# Gyro.net
KiCad netlist of a schematic drawn in Altium Designer
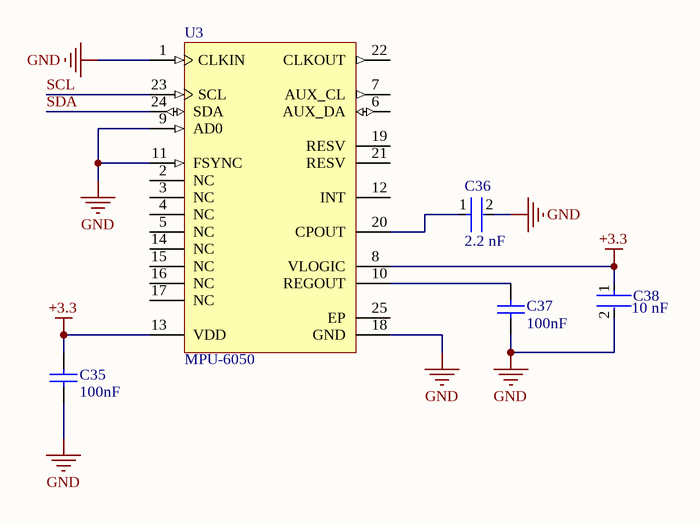
[diagram p0: Gyro.SchDoc]

(export (version "E")
  (design (tool "Eeschema 10.0.6"))
  (components
    (comp (ref "C35")
      (value "CL05B104KO5NNNC")
      (footprint "CAPC1050X55X23ML05T13")
      (description "Chip Capacitor, 100 nF, +/- 10%, 16 V, -55 to 125 degC, 0402 (1005 Metric), RoHS, Tape and Reel")
      (fields (field (name "MANUFACTURER") "Samsung Electro-Mechanics") (field (name "CAPACITANCE") "100nF"))
      (libsource (lib "Altium Content Vault") (part "CAP-NP-2"))
    )
    (comp (ref "C36")
      (value "CC0402KRX7R9BB222")
      (footprint "FP-CC0402-MFG")
      (description "CAP CER 2200PF 50V X7R 0402")
      (fields
        (field (name "TOLERANCE") "0.1")
        (field (name "OCTOPART") "https://octopart.com/cc0402krx7r9bb222-yageo-39467642")
        (field (name "CAPACITANCE") "2.2 nF")
      )
      (libsource (lib "Altium Content Vault") (part "11868f565c42a9108669ba33697ecf6"))
    )
    (comp (ref "C37")
      (value "CL05B104KO5NNNC")
      (footprint "CAPC1050X55X23ML05T13")
      (description "Chip Capacitor, 100 nF, +/- 10%, 16 V, -55 to 125 degC, 0402 (1005 Metric), RoHS, Tape and Reel")
      (fields (field (name "MANUFACTURER") "Samsung Electro-Mechanics") (field (name "CAPACITANCE") "100nF"))
      (libsource (lib "Altium Content Vault") (part "CAP-NP-2"))
    )
    (comp (ref "C38")
      (value "CC0402KRX7R9BB103")
      (footprint "FP-CC0402-MFG")
      (description "CAP CER 10000PF 50V X7R 0402")
      (fields
        (field (name "OCTOPART") "https://octopart.com/cc0402krx7r9bb103-yageo-8376513")
        (field (name "CAPACITANCE") "10 nF")
        (field (name "MANUFACTURER") "YAGEO")
      )
      (libsource (lib "Altium Content Vault") (part "11868f565c42a9108669ba33697ecf6"))
    )
    (comp (ref "U3")
      (value "MPU-6050")
      (footprint "IS-QFN-24_V")
      (fields (field (name "MANUFACTURER") "InvenSense"))
      (libsource (lib "Altium Content Vault") (part "IS-MPU-6050-QFN-24"))
    )
  )
  (nets
    (net (code "1") (name "+3.3") (class "Default")
      (node (ref "C35") (pin "2") (pinfunction "2_2") (pintype "passive"))
      (node (ref "C38") (pin "1") (pinfunction "1_1") (pintype "passive"))
      (node (ref "U3") (pin "13") (pinfunction "VDD_13") (pintype "power_in"))
      (node (ref "U3") (pin "8") (pinfunction "VLOGIC_8") (pintype "power_in"))
    )
    (net (code "2") (name "/SCL") (class "Default")
      (node (ref "U3") (pin "23") (pinfunction "SCL_23") (pintype "input"))
    )
    (net (code "3") (name "/SDA") (class "Default")
      (node (ref "U3") (pin "24") (pinfunction "SDA_24") (pintype "bidirectional"))
    )
    (net (code "4") (name "GND") (class "Default")
      (node (ref "C35") (pin "1") (pinfunction "1_1") (pintype "passive"))
      (node (ref "C36") (pin "2") (pinfunction "2_2") (pintype "passive"))
      (node (ref "C37") (pin "1") (pinfunction "1_1") (pintype "passive"))
      (node (ref "C38") (pin "2") (pinfunction "2_2") (pintype "passive"))
      (node (ref "U3") (pin "1") (pinfunction "CLKIN_1") (pintype "input"))
      (node (ref "U3") (pin "11") (pinfunction "FSYNC_11") (pintype "input"))
      (node (ref "U3") (pin "18") (pinfunction "GND_18") (pintype "power_in"))
      (node (ref "U3") (pin "9") (pinfunction "AD0_9") (pintype "input"))
    )
    (net (code "5") (name "Net-(U3-CPOUT)") (class "Default")
      (node (ref "C36") (pin "1") (pinfunction "1_1") (pintype "passive"))
      (node (ref "U3") (pin "20") (pinfunction "CPOUT_20") (pintype "passive"))
    )
    (net (code "6") (name "Net-(U3-REGOUT)") (class "Default")
      (node (ref "C37") (pin "2") (pinfunction "2_2") (pintype "passive"))
      (node (ref "U3") (pin "10") (pinfunction "REGOUT_10") (pintype "passive"))
    )
    (net (code "7") (name "unconnected-(U3-AUX_CL-Pad7)") (class "Default")
      (node (ref "U3") (pin "7") (pinfunction "AUX_CL_7") (pintype "output"))
    )
    (net (code "8") (name "unconnected-(U3-AUX_DA-Pad6)") (class "Default")
      (node (ref "U3") (pin "6") (pinfunction "AUX_DA_6") (pintype "bidirectional"))
    )
    (net (code "9") (name "unconnected-(U3-CLKOUT-Pad22)") (class "Default")
      (node (ref "U3") (pin "22") (pinfunction "CLKOUT_22") (pintype "output"))
    )
    (net (code "10") (name "unconnected-(U3-EP-Pad25)") (class "Default")
      (node (ref "U3") (pin "25") (pinfunction "EP_25") (pintype "power_in"))
    )
    (net (code "11") (name "unconnected-(U3-INT-Pad12)") (class "Default")
      (node (ref "U3") (pin "12") (pinfunction "INT_12") (pintype "open_collector"))
    )
    (net (code "12") (name "unconnected-(U3-NC-Pad2)") (class "Default")
      (node (ref "U3") (pin "2") (pinfunction "NC_2") (pintype "passive"))
    )
    (net (code "13") (name "unconnected-(U3-NC-Pad3)") (class "Default")
      (node (ref "U3") (pin "3") (pinfunction "NC_3") (pintype "passive"))
    )
    (net (code "14") (name "unconnected-(U3-NC-Pad4)") (class "Default")
      (node (ref "U3") (pin "4") (pinfunction "NC_4") (pintype "passive"))
    )
    (net (code "15") (name "unconnected-(U3-NC-Pad5)") (class "Default")
      (node (ref "U3") (pin "5") (pinfunction "NC_5") (pintype "passive"))
    )
    (net (code "16") (name "unconnected-(U3-NC-Pad14)") (class "Default")
      (node (ref "U3") (pin "14") (pinfunction "NC_14") (pintype "passive"))
    )
    (net (code "17") (name "unconnected-(U3-NC-Pad15)") (class "Default")
      (node (ref "U3") (pin "15") (pinfunction "NC_15") (pintype "passive"))
    )
    (net (code "18") (name "unconnected-(U3-NC-Pad16)") (class "Default")
      (node (ref "U3") (pin "16") (pinfunction "NC_16") (pintype "passive"))
    )
    (net (code "19") (name "unconnected-(U3-NC-Pad17)") (class "Default")
      (node (ref "U3") (pin "17") (pinfunction "NC_17") (pintype "passive"))
    )
    (net (code "20") (name "unconnected-(U3-RESV-Pad19)") (class "Default")
      (node (ref "U3") (pin "19") (pinfunction "RESV_19") (pintype "passive"))
    )
    (net (code "21") (name "unconnected-(U3-RESV-Pad21)") (class "Default")
      (node (ref "U3") (pin "21") (pinfunction "RESV_21") (pintype "passive"))
    )
  )
)
